# v1_0.net
KiCad netlist of a schematic drawn in EAGLE
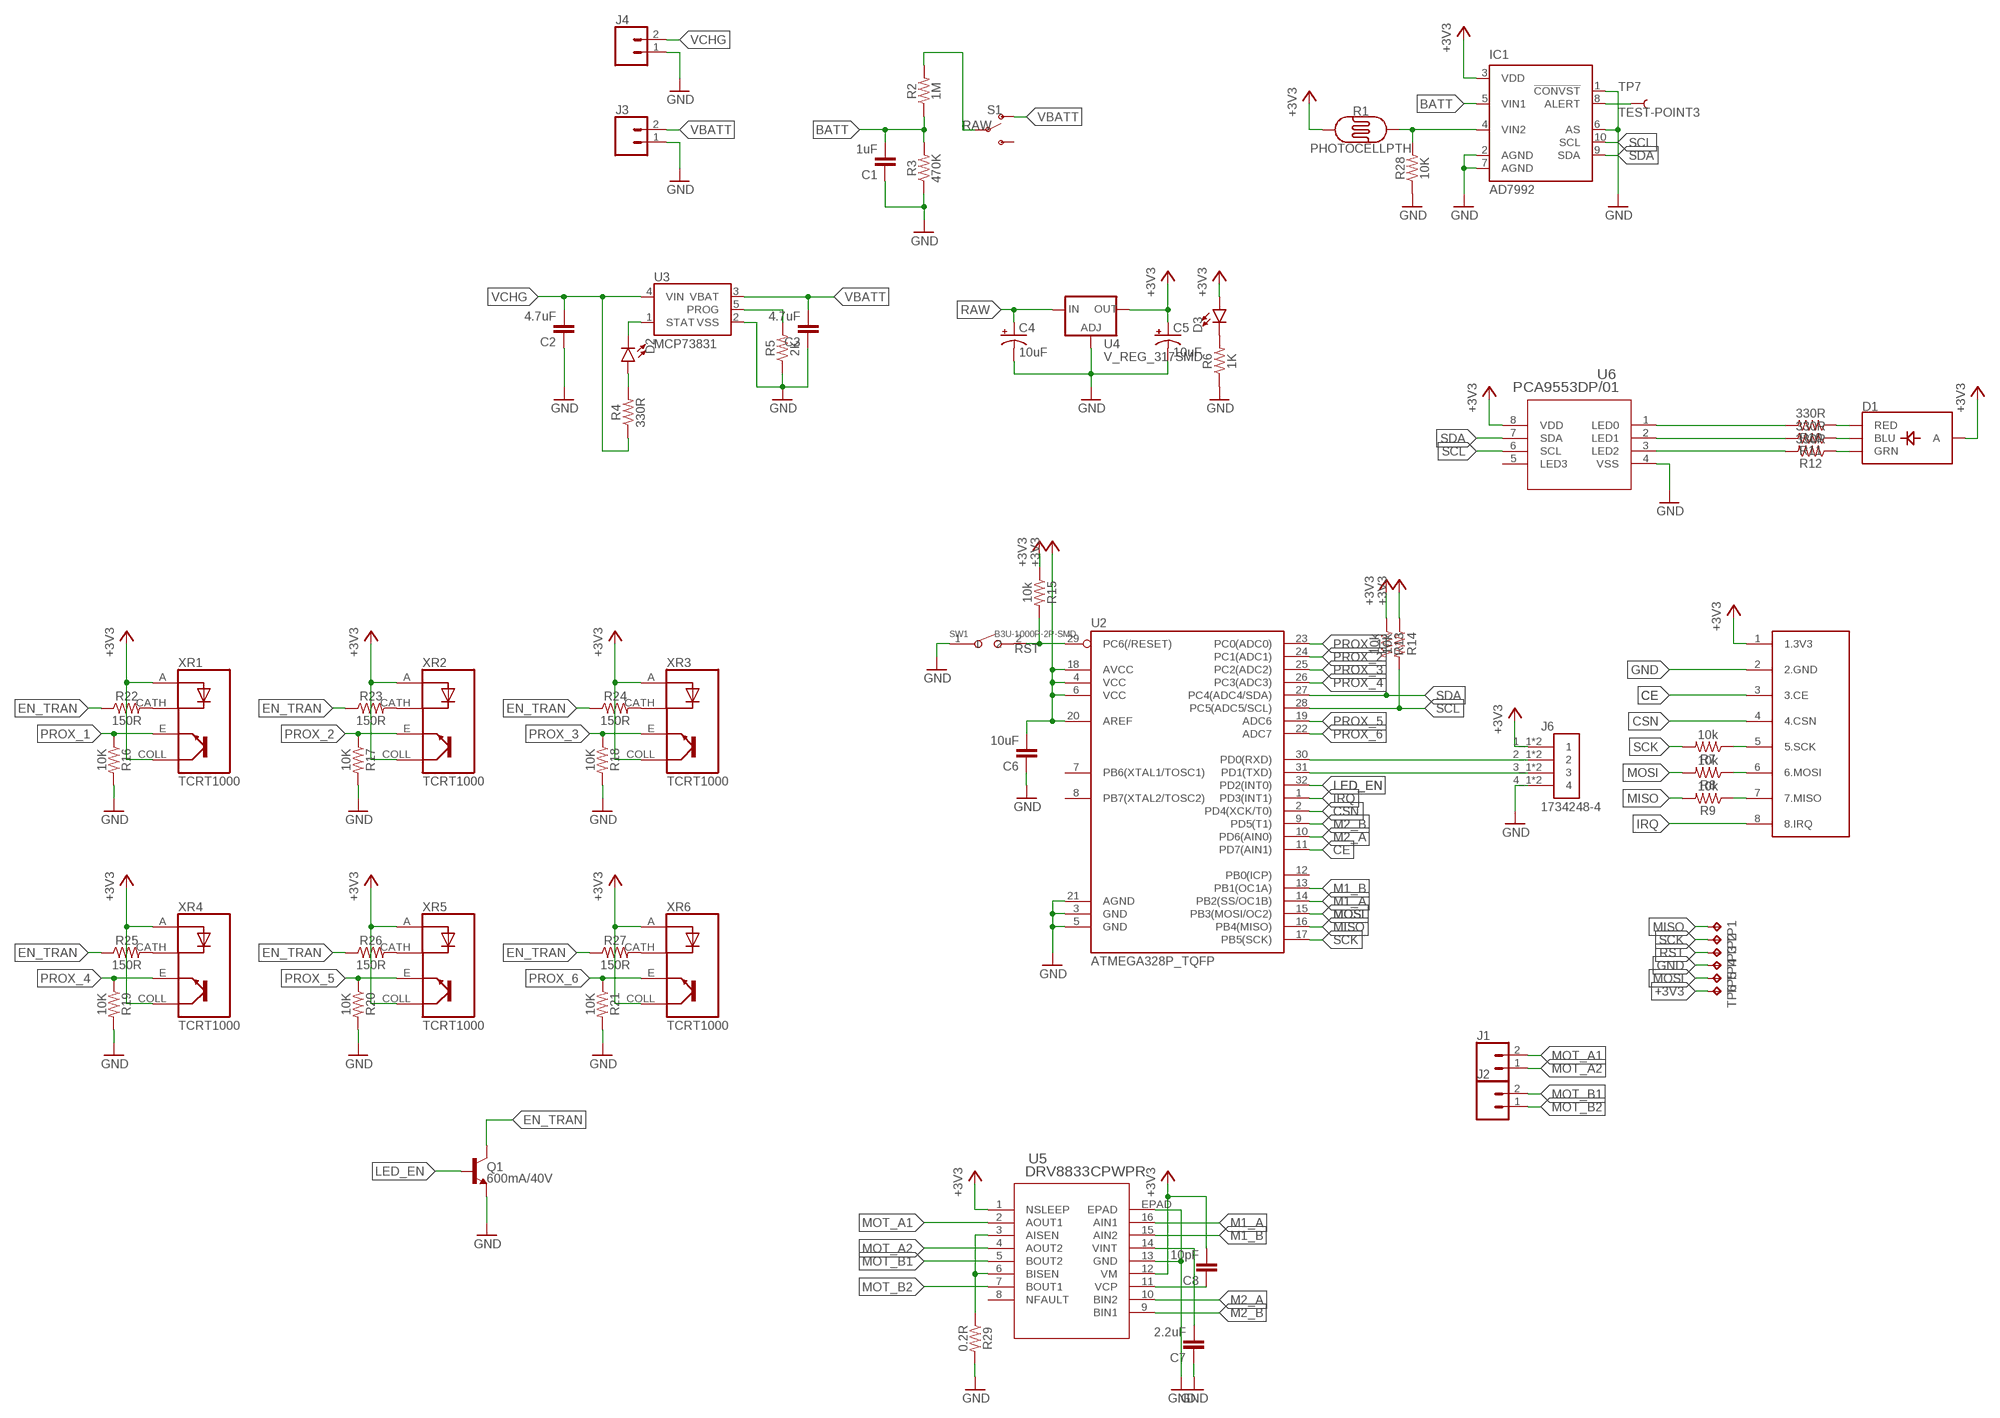
[diagram p0: schematic, sheet 1]

(export (version "E")
  (design (tool "Eeschema 10.0.6"))
  (components
    (comp (ref "C1")
      (value "1uF")
      (footprint "eagle-import:C0603")
      (libsource (lib "eagle-import") (part "C-EUC0603"))
    )
    (comp (ref "C2")
      (value "4.7uF")
      (footprint "eagle-import:C0603")
      (libsource (lib "eagle-import") (part "C-EUC0603"))
    )
    (comp (ref "C3")
      (value "4.7uF")
      (footprint "eagle-import:C0603")
      (libsource (lib "eagle-import") (part "C-EUC0603"))
    )
    (comp (ref "C4")
      (value "10uF")
      (footprint "eagle-import:EIA3216")
      (libsource (lib "eagle-import") (part "10UF-POLAR-EIA3216-16V-10%(TANT)"))
    )
    (comp (ref "C5")
      (value "10uF")
      (footprint "eagle-import:EIA3216")
      (libsource (lib "eagle-import") (part "10UF-POLAR-EIA3216-16V-10%(TANT)"))
    )
    (comp (ref "C6")
      (value "10uF")
      (footprint "eagle-import:C0603")
      (libsource (lib "eagle-import") (part "C-EUC0603"))
    )
    (comp (ref "C7")
      (value "2.2uF")
      (footprint "eagle-import:C0603")
      (libsource (lib "eagle-import") (part "C-EUC0603"))
    )
    (comp (ref "C8")
      (value "10pF")
      (footprint "eagle-import:C0603")
      (libsource (lib "eagle-import") (part "C-EUC0603"))
    )
    (comp (ref "D1")
      (value "LED-RGB-CASMD")
      (footprint "eagle-import:LED-TRICOLOR-SMD")
      (libsource (lib "eagle-import") (part "LED-RGB-CASMD"))
    )
    (comp (ref "D2")
      (value "LED0603")
      (footprint "eagle-import:LED-0603")
      (libsource (lib "eagle-import") (part "LED0603"))
    )
    (comp (ref "D3")
      (value "LED0603")
      (footprint "eagle-import:LED-0603")
      (libsource (lib "eagle-import") (part "LED0603"))
    )
    (comp (ref "IC1")
      (value "AD7992")
      (footprint "eagle-import:MSOP10")
      (fields (field (name "MPN") "AD7992BRMZ-0"))
      (libsource (lib "eagle-import") (part "AD7992"))
    )
    (comp (ref "J1")
      (value "CONN_02")
      (footprint "eagle-import:1X02")
      (libsource (lib "eagle-import") (part "CONN_02"))
    )
    (comp (ref "J2")
      (value "CONN_02")
      (footprint "eagle-import:1X02")
      (libsource (lib "eagle-import") (part "CONN_02"))
    )
    (comp (ref "J3")
      (value "CONN_02")
      (footprint "eagle-import:1X02")
      (libsource (lib "eagle-import") (part "CONN_02"))
    )
    (comp (ref "J4")
      (value "CONN_02")
      (footprint "eagle-import:1X02")
      (libsource (lib "eagle-import") (part "CONN_02"))
    )
    (comp (ref "J6")
      (value "1734248-4")
      (footprint "eagle-import:TE_1734248-4")
      (fields (field (name "DIGI-KEY_PART_NUMBER") "A101414CT-ND") (field (name "MF") "TE Connectivity"))
      (libsource (lib "eagle-import") (part "1734248-4"))
    )
    (comp (ref "Q1")
      (value "600mA/40V")
      (footprint "eagle-import:SOT23-3")
      (libsource (lib "eagle-import") (part "TRANS_NPN-MMBT2222AL"))
    )
    (comp (ref "R1")
      (value "PHOTOCELLPTH")
      (footprint "eagle-import:PHOTOCELL")
      (libsource (lib "eagle-import") (part "PHOTOCELLPTH"))
    )
    (comp (ref "R2")
      (value "1M")
      (footprint "eagle-import:0402")
      (libsource (lib "eagle-import") (part "RESISTOR0402"))
    )
    (comp (ref "R3")
      (value "470K")
      (footprint "eagle-import:0402")
      (libsource (lib "eagle-import") (part "RESISTOR0402"))
    )
    (comp (ref "R4")
      (value "330R")
      (footprint "eagle-import:0402")
      (libsource (lib "eagle-import") (part "RESISTOR0402"))
    )
    (comp (ref "R5")
      (value "2K")
      (footprint "eagle-import:0402")
      (libsource (lib "eagle-import") (part "RESISTOR0402"))
    )
    (comp (ref "R6")
      (value "1K")
      (footprint "eagle-import:0402")
      (libsource (lib "eagle-import") (part "RESISTOR0402"))
    )
    (comp (ref "R7")
      (value "10k")
      (footprint "eagle-import:0402")
      (libsource (lib "eagle-import") (part "RESISTOR0402"))
    )
    (comp (ref "R8")
      (value "10k")
      (footprint "eagle-import:0402")
      (libsource (lib "eagle-import") (part "RESISTOR0402"))
    )
    (comp (ref "R9")
      (value "10k")
      (footprint "eagle-import:0402")
      (libsource (lib "eagle-import") (part "RESISTOR0402"))
    )
    (comp (ref "R10")
      (value "330R")
      (footprint "eagle-import:0402")
      (libsource (lib "eagle-import") (part "RESISTOR0402"))
    )
    (comp (ref "R11")
      (value "330R")
      (footprint "eagle-import:0402")
      (libsource (lib "eagle-import") (part "RESISTOR0402"))
    )
    (comp (ref "R12")
      (value "330R")
      (footprint "eagle-import:0402")
      (libsource (lib "eagle-import") (part "RESISTOR0402"))
    )
    (comp (ref "R13")
      (value "10k")
      (footprint "eagle-import:0402")
      (libsource (lib "eagle-import") (part "RESISTOR0402"))
    )
    (comp (ref "R14")
      (value "10k")
      (footprint "eagle-import:0402")
      (libsource (lib "eagle-import") (part "RESISTOR0402"))
    )
    (comp (ref "R15")
      (value "10k")
      (footprint "eagle-import:0402")
      (libsource (lib "eagle-import") (part "RESISTOR0402"))
    )
    (comp (ref "R16")
      (value "10K")
      (footprint "eagle-import:0402")
      (libsource (lib "eagle-import") (part "RESISTOR0402"))
    )
    (comp (ref "R17")
      (value "10K")
      (footprint "eagle-import:0402")
      (libsource (lib "eagle-import") (part "RESISTOR0402"))
    )
    (comp (ref "R18")
      (value "10K")
      (footprint "eagle-import:0402")
      (libsource (lib "eagle-import") (part "RESISTOR0402"))
    )
    (comp (ref "R19")
      (value "10K")
      (footprint "eagle-import:0402")
      (libsource (lib "eagle-import") (part "RESISTOR0402"))
    )
    (comp (ref "R20")
      (value "10K")
      (footprint "eagle-import:0402")
      (libsource (lib "eagle-import") (part "RESISTOR0402"))
    )
    (comp (ref "R21")
      (value "10K")
      (footprint "eagle-import:0402")
      (libsource (lib "eagle-import") (part "RESISTOR0402"))
    )
    (comp (ref "R22")
      (value "150R")
      (footprint "eagle-import:0402")
      (libsource (lib "eagle-import") (part "RESISTOR0402"))
    )
    (comp (ref "R23")
      (value "150R")
      (footprint "eagle-import:0402")
      (libsource (lib "eagle-import") (part "RESISTOR0402"))
    )
    (comp (ref "R24")
      (value "150R")
      (footprint "eagle-import:0402")
      (libsource (lib "eagle-import") (part "RESISTOR0402"))
    )
    (comp (ref "R25")
      (value "150R")
      (footprint "eagle-import:0402")
      (libsource (lib "eagle-import") (part "RESISTOR0402"))
    )
    (comp (ref "R26")
      (value "150R")
      (footprint "eagle-import:0402")
      (libsource (lib "eagle-import") (part "RESISTOR0402"))
    )
    (comp (ref "R27")
      (value "150R")
      (footprint "eagle-import:0402")
      (libsource (lib "eagle-import") (part "RESISTOR0402"))
    )
    (comp (ref "R28")
      (value "10K")
      (footprint "eagle-import:0402")
      (libsource (lib "eagle-import") (part "RESISTOR0402"))
    )
    (comp (ref "R29")
      (value "0.2R")
      (footprint "eagle-import:0402")
      (libsource (lib "eagle-import") (part "RESISTOR0402"))
    )
    (comp (ref "S1")
      (value "SWITCH-SPDT-SMD-RIGHT-ANGLE")
      (footprint "eagle-import:SWITCH_SPST_SMD_A")
      (libsource (lib "eagle-import") (part "SWITCH-SPDT-SMD-RIGHT-ANGLE"))
    )
    (comp (ref "SW1")
      (value "B3U-1000P-2P-SMD")
      (footprint "eagle-import:SW2-2.6-3.0X2.5X1.2+0.4MM")
      (libsource (lib "eagle-import") (part "SMD-BUTTON(2P-3.0X2.5X1.2+0.4MM)-B3U-1000P-2P-SMD"))
    )
    (comp (ref "TP1")
      (value "TPB1,27")
      (footprint "eagle-import:B1,27")
      (libsource (lib "eagle-import") (part "TPB1,27"))
    )
    (comp (ref "TP2")
      (value "TPB1,27")
      (footprint "eagle-import:B1,27")
      (libsource (lib "eagle-import") (part "TPB1,27"))
    )
    (comp (ref "TP3")
      (value "TPB1,27")
      (footprint "eagle-import:B1,27")
      (libsource (lib "eagle-import") (part "TPB1,27"))
    )
    (comp (ref "TP4")
      (value "TPB1,27")
      (footprint "eagle-import:B1,27")
      (libsource (lib "eagle-import") (part "TPB1,27"))
    )
    (comp (ref "TP5")
      (value "TPB1,27")
      (footprint "eagle-import:B1,27")
      (libsource (lib "eagle-import") (part "TPB1,27"))
    )
    (comp (ref "TP6")
      (value "TPB1,27")
      (footprint "eagle-import:B1,27")
      (libsource (lib "eagle-import") (part "TPB1,27"))
    )
    (comp (ref "TP7")
      (value "TEST-POINT3")
      (footprint "eagle-import:PAD.03X.03")
      (libsource (lib "eagle-import") (part "TEST-POINT3"))
    )
    (comp (ref "U$1")
      (value "NRF24L01+")
      (footprint "eagle-import:NRF24L01+")
      (libsource (lib "eagle-import") (part "NRF24L01+"))
    )
    (comp (ref "U2")
      (value "ATMEGA328P_TQFP")
      (footprint "eagle-import:TQFP32-08")
      (libsource (lib "eagle-import") (part "ATMEGA328P_TQFP"))
    )
    (comp (ref "U3")
      (value "MCP73831")
      (footprint "eagle-import:SOT23-5")
      (libsource (lib "eagle-import") (part "MCP73831"))
    )
    (comp (ref "U4")
      (value "V_REG_317SMD")
      (footprint "eagle-import:SOT223")
      (libsource (lib "eagle-import") (part "V_REG_317SMD"))
    )
    (comp (ref "U5")
      (value "DRV8833CPWPR")
      (footprint "eagle-import:PWP16_2P31X2P46")
      (libsource (lib "eagle-import") (part "DRV8833CPWPR"))
    )
    (comp (ref "U6")
      (value "PCA9553DP/01")
      (footprint "eagle-import:SOT505-1")
      (fields (field (name "MANUFACTURER_PART_NUMBER") "PCA9553DP01"))
      (libsource (lib "eagle-import") (part "PCA9553DP/01"))
    )
    (comp (ref "XR1")
      (value "TCRT1000")
      (footprint "eagle-import:XDCR_TCRT1000")
      (fields (field (name "MF") "Vishay"))
      (libsource (lib "eagle-import") (part "TCRT1000"))
    )
    (comp (ref "XR2")
      (value "TCRT1000")
      (footprint "eagle-import:XDCR_TCRT1000")
      (fields (field (name "MF") "Vishay"))
      (libsource (lib "eagle-import") (part "TCRT1000"))
    )
    (comp (ref "XR3")
      (value "TCRT1000")
      (footprint "eagle-import:XDCR_TCRT1000")
      (fields (field (name "MF") "Vishay"))
      (libsource (lib "eagle-import") (part "TCRT1000"))
    )
    (comp (ref "XR4")
      (value "TCRT1000")
      (footprint "eagle-import:XDCR_TCRT1000")
      (fields (field (name "MF") "Vishay"))
      (libsource (lib "eagle-import") (part "TCRT1000"))
    )
    (comp (ref "XR5")
      (value "TCRT1000")
      (footprint "eagle-import:XDCR_TCRT1000")
      (fields (field (name "MF") "Vishay"))
      (libsource (lib "eagle-import") (part "TCRT1000"))
    )
    (comp (ref "XR6")
      (value "TCRT1000")
      (footprint "eagle-import:XDCR_TCRT1000")
      (fields (field (name "MF") "Vishay"))
      (libsource (lib "eagle-import") (part "TCRT1000"))
    )
  )
  (nets
    (net (code "1") (name "+3V3") (class "Default")
      (node (ref "C5") (pin "+") (pinfunction "+_+") (pintype "passive"))
      (node (ref "C6") (pin "2") (pinfunction "2_2") (pintype "passive"))
      (node (ref "C8") (pin "2") (pinfunction "2_2") (pintype "passive"))
      (node (ref "D1") (pin "A") (pinfunction "A_A") (pintype "bidirectional"))
      (node (ref "D3") (pin "A") (pinfunction "A_A") (pintype "passive"))
      (node (ref "IC1") (pin "3") (pinfunction "VDD_3") (pintype "power_in"))
      (node (ref "J6") (pin "1_1") (pinfunction "1_1_1") (pintype "passive"))
      (node (ref "J6") (pin "1_2") (pinfunction "1_1_2") (pintype "passive"))
      (node (ref "R1") (pin "1") (pinfunction "P$1_1") (pintype "bidirectional"))
      (node (ref "R13") (pin "1") (pinfunction "1_1") (pintype "passive"))
      (node (ref "R14") (pin "1") (pinfunction "1_1") (pintype "passive"))
      (node (ref "R15") (pin "1") (pinfunction "1_1") (pintype "passive"))
      (node (ref "TP6") (pin "TP") (pinfunction "TP_TP") (pintype "input"))
      (node (ref "U$1") (pin "1") (pinfunction "1.3V3_1") (pintype "bidirectional"))
      (node (ref "U2") (pin "18") (pinfunction "AVCC_18") (pintype "bidirectional"))
      (node (ref "U2") (pin "20") (pinfunction "AREF_20") (pintype "bidirectional"))
      (node (ref "U2") (pin "4") (pinfunction "VCC_4") (pintype "bidirectional"))
      (node (ref "U2") (pin "6") (pinfunction "VCC_6") (pintype "bidirectional"))
      (node (ref "U4") (pin "2") (pinfunction "OUT_2") (pintype "output"))
      (node (ref "U5") (pin "1") (pinfunction "NSLEEP_1") (pintype "input"))
      (node (ref "U5") (pin "12") (pinfunction "VM_12") (pintype "power_in"))
      (node (ref "U6") (pin "8") (pinfunction "VDD_8") (pintype "passive"))
      (node (ref "XR1") (pin "A") (pinfunction "A_A") (pintype "passive"))
      (node (ref "XR1") (pin "COLL") (pinfunction "CO_COLL") (pintype "passive"))
      (node (ref "XR2") (pin "A") (pinfunction "A_A") (pintype "passive"))
      (node (ref "XR2") (pin "COLL") (pinfunction "CO_COLL") (pintype "passive"))
      (node (ref "XR3") (pin "A") (pinfunction "A_A") (pintype "passive"))
      (node (ref "XR3") (pin "COLL") (pinfunction "CO_COLL") (pintype "passive"))
      (node (ref "XR4") (pin "A") (pinfunction "A_A") (pintype "passive"))
      (node (ref "XR4") (pin "COLL") (pinfunction "CO_COLL") (pintype "passive"))
      (node (ref "XR5") (pin "A") (pinfunction "A_A") (pintype "passive"))
      (node (ref "XR5") (pin "COLL") (pinfunction "CO_COLL") (pintype "passive"))
      (node (ref "XR6") (pin "A") (pinfunction "A_A") (pintype "passive"))
      (node (ref "XR6") (pin "COLL") (pinfunction "CO_COLL") (pintype "passive"))
    )
    (net (code "2") (name "BATT") (class "Default")
      (node (ref "C1") (pin "2") (pinfunction "2_2") (pintype "passive"))
      (node (ref "IC1") (pin "5") (pinfunction "VIN1_5") (pintype "input"))
      (node (ref "R2") (pin "1") (pinfunction "1_1") (pintype "passive"))
      (node (ref "R3") (pin "2") (pinfunction "2_2") (pintype "passive"))
    )
    (net (code "3") (name "CE") (class "Default")
      (node (ref "U$1") (pin "3") (pinfunction "3.CE_3") (pintype "bidirectional"))
      (node (ref "U2") (pin "11") (pinfunction "PD7(AIN1)_11") (pintype "bidirectional"))
    )
    (net (code "4") (name "CSN") (class "Default")
      (node (ref "U$1") (pin "4") (pinfunction "4.CSN_4") (pintype "bidirectional"))
      (node (ref "U2") (pin "2") (pinfunction "PD4(XCK/T0)_2") (pintype "bidirectional"))
    )
    (net (code "5") (name "EN_TRAN") (class "Default")
      (node (ref "Q1") (pin "3") (pinfunction "C_3") (pintype "passive"))
      (node (ref "R22") (pin "1") (pinfunction "1_1") (pintype "passive"))
      (node (ref "R23") (pin "1") (pinfunction "1_1") (pintype "passive"))
      (node (ref "R24") (pin "1") (pinfunction "1_1") (pintype "passive"))
      (node (ref "R25") (pin "1") (pinfunction "1_1") (pintype "passive"))
      (node (ref "R26") (pin "1") (pinfunction "1_1") (pintype "passive"))
      (node (ref "R27") (pin "1") (pinfunction "1_1") (pintype "passive"))
    )
    (net (code "6") (name "GND") (class "Default")
      (node (ref "C1") (pin "1") (pinfunction "1_1") (pintype "passive"))
      (node (ref "C2") (pin "1") (pinfunction "1_1") (pintype "passive"))
      (node (ref "C3") (pin "1") (pinfunction "1_1") (pintype "passive"))
      (node (ref "C4") (pin "-") (pinfunction "-_-") (pintype "passive"))
      (node (ref "C5") (pin "-") (pinfunction "-_-") (pintype "passive"))
      (node (ref "C6") (pin "1") (pinfunction "1_1") (pintype "passive"))
      (node (ref "C7") (pin "1") (pinfunction "1_1") (pintype "passive"))
      (node (ref "IC1") (pin "1") (pinfunction "~{CONVST}_1") (pintype "input"))
      (node (ref "IC1") (pin "2") (pinfunction "AGND_2") (pintype "power_in"))
      (node (ref "IC1") (pin "6") (pinfunction "AS_6") (pintype "input"))
      (node (ref "IC1") (pin "7") (pinfunction "AGND_7") (pintype "power_in"))
      (node (ref "J3") (pin "1") (pinfunction "1_1") (pintype "passive"))
      (node (ref "J4") (pin "1") (pinfunction "1_1") (pintype "passive"))
      (node (ref "J6") (pin "4_1") (pinfunction "4_4_1") (pintype "passive"))
      (node (ref "J6") (pin "4_2") (pinfunction "4_4_2") (pintype "passive"))
      (node (ref "Q1") (pin "2") (pinfunction "E_2") (pintype "passive"))
      (node (ref "R16") (pin "2") (pinfunction "2_2") (pintype "passive"))
      (node (ref "R17") (pin "2") (pinfunction "2_2") (pintype "passive"))
      (node (ref "R18") (pin "2") (pinfunction "2_2") (pintype "passive"))
      (node (ref "R19") (pin "2") (pinfunction "2_2") (pintype "passive"))
      (node (ref "R20") (pin "2") (pinfunction "2_2") (pintype "passive"))
      (node (ref "R21") (pin "2") (pinfunction "2_2") (pintype "passive"))
      (node (ref "R28") (pin "1") (pinfunction "1_1") (pintype "passive"))
      (node (ref "R29") (pin "2") (pinfunction "2_2") (pintype "passive"))
      (node (ref "R3") (pin "1") (pinfunction "1_1") (pintype "passive"))
      (node (ref "R5") (pin "1") (pinfunction "1_1") (pintype "passive"))
      (node (ref "R6") (pin "1") (pinfunction "1_1") (pintype "passive"))
      (node (ref "SW1") (pin "1") (pinfunction "1_1") (pintype "bidirectional"))
      (node (ref "TP4") (pin "TP") (pinfunction "TP_TP") (pintype "input"))
      (node (ref "U$1") (pin "2") (pinfunction "2.GND_2") (pintype "bidirectional"))
      (node (ref "U2") (pin "21") (pinfunction "AGND_21") (pintype "bidirectional"))
      (node (ref "U2") (pin "3") (pinfunction "GND_3") (pintype "bidirectional"))
      (node (ref "U2") (pin "5") (pinfunction "GND_5") (pintype "bidirectional"))
      (node (ref "U3") (pin "2") (pinfunction "VSS_2") (pintype "power_in"))
      (node (ref "U4") (pin "1") (pinfunction "ADJ_1") (pintype "input"))
      (node (ref "U5") (pin "13") (pinfunction "GND_13") (pintype "power_in"))
      (node (ref "U5") (pin "EPAD") (pinfunction "EPAD_EPAD") (pintype "passive"))
      (node (ref "U6") (pin "4") (pinfunction "VSS_4") (pintype "passive"))
    )
    (net (code "7") (name "IRQ") (class "Default")
      (node (ref "U$1") (pin "8") (pinfunction "8.IRQ_8") (pintype "bidirectional"))
      (node (ref "U2") (pin "1") (pinfunction "PD3(INT1)_1") (pintype "bidirectional"))
    )
    (net (code "8") (name "LED_EN") (class "Default")
      (node (ref "Q1") (pin "1") (pinfunction "B_1") (pintype "passive"))
      (node (ref "U2") (pin "32") (pinfunction "PD2(INT0)_32") (pintype "bidirectional"))
    )
    (net (code "9") (name "M1_A") (class "Default")
      (node (ref "U2") (pin "14") (pinfunction "PB2(SS/OC1B)_14") (pintype "bidirectional"))
      (node (ref "U5") (pin "16") (pinfunction "AIN1_16") (pintype "input"))
    )
    (net (code "10") (name "M1_B") (class "Default")
      (node (ref "U2") (pin "13") (pinfunction "PB1(OC1A)_13") (pintype "bidirectional"))
      (node (ref "U5") (pin "15") (pinfunction "AIN2_15") (pintype "input"))
    )
    (net (code "11") (name "M2_A") (class "Default")
      (node (ref "U2") (pin "10") (pinfunction "PD6(AIN0)_10") (pintype "bidirectional"))
      (node (ref "U5") (pin "10") (pinfunction "BIN2_10") (pintype "input"))
    )
    (net (code "12") (name "M2_B") (class "Default")
      (node (ref "U2") (pin "9") (pinfunction "PD5(T1)_9") (pintype "bidirectional"))
      (node (ref "U5") (pin "9") (pinfunction "BIN1_9") (pintype "input"))
    )
    (net (code "13") (name "MISO") (class "Default")
      (node (ref "R9") (pin "2") (pinfunction "2_2") (pintype "passive"))
      (node (ref "TP1") (pin "TP") (pinfunction "TP_TP") (pintype "input"))
      (node (ref "U2") (pin "16") (pinfunction "PB4(MISO)_16") (pintype "bidirectional"))
    )
    (net (code "14") (name "MOSI") (class "Default")
      (node (ref "R8") (pin "2") (pinfunction "2_2") (pintype "passive"))
      (node (ref "TP5") (pin "TP") (pinfunction "TP_TP") (pintype "input"))
      (node (ref "U2") (pin "15") (pinfunction "PB3(MOSI/OC2)_15") (pintype "bidirectional"))
    )
    (net (code "15") (name "MOT_A1") (class "Default")
      (node (ref "J1") (pin "2") (pinfunction "2_2") (pintype "passive"))
      (node (ref "U5") (pin "2") (pinfunction "AOUT1_2") (pintype "output"))
    )
    (net (code "16") (name "MOT_A2") (class "Default")
      (node (ref "J1") (pin "1") (pinfunction "1_1") (pintype "passive"))
      (node (ref "U5") (pin "4") (pinfunction "AOUT2_4") (pintype "output"))
    )
    (net (code "17") (name "MOT_B1") (class "Default")
      (node (ref "J2") (pin "2") (pinfunction "2_2") (pintype "passive"))
      (node (ref "U5") (pin "5") (pinfunction "BOUT2_5") (pintype "output"))
    )
    (net (code "18") (name "MOT_B2") (class "Default")
      (node (ref "J2") (pin "1") (pinfunction "1_1") (pintype "passive"))
      (node (ref "U5") (pin "7") (pinfunction "BOUT1_7") (pintype "output"))
    )
    (net (code "19") (name "Net-(D1-BLU)") (class "Default")
      (node (ref "D1") (pin "B") (pinfunction "BLU_B") (pintype "bidirectional"))
      (node (ref "R11") (pin "1") (pinfunction "1_1") (pintype "passive"))
    )
    (net (code "20") (name "Net-(D1-GRN)") (class "Default")
      (node (ref "D1") (pin "G") (pinfunction "GRN_G") (pintype "bidirectional"))
      (node (ref "R12") (pin "1") (pinfunction "1_1") (pintype "passive"))
    )
    (net (code "21") (name "Net-(D1-RED)") (class "Default")
      (node (ref "D1") (pin "R") (pinfunction "RED_R") (pintype "bidirectional"))
      (node (ref "R10") (pin "1") (pinfunction "1_1") (pintype "passive"))
    )
    (net (code "22") (name "Net-(D2-PadA)") (class "Default")
      (node (ref "D2") (pin "A") (pinfunction "A_A") (pintype "passive"))
      (node (ref "R4") (pin "2") (pinfunction "2_2") (pintype "passive"))
    )
    (net (code "23") (name "Net-(D3-PadC)") (class "Default")
      (node (ref "D3") (pin "C") (pinfunction "C_C") (pintype "passive"))
      (node (ref "R6") (pin "2") (pinfunction "2_2") (pintype "passive"))
    )
    (net (code "24") (name "Net-(IC1-ALERT)") (class "Default")
      (node (ref "IC1") (pin "8") (pinfunction "ALERT_8") (pintype "output"))
      (node (ref "TP7") (pin "P$1") (pinfunction "1_P$1") (pintype "bidirectional"))
    )
    (net (code "25") (name "Net-(IC1-VIN2)") (class "Default")
      (node (ref "IC1") (pin "4") (pinfunction "VIN2_4") (pintype "input"))
      (node (ref "R1") (pin "2") (pinfunction "P$2_2") (pintype "bidirectional"))
      (node (ref "R28") (pin "2") (pinfunction "2_2") (pintype "passive"))
    )
    (net (code "26") (name "Net-(U$1-5.SCK)") (class "Default")
      (node (ref "R7") (pin "1") (pinfunction "1_1") (pintype "passive"))
      (node (ref "U$1") (pin "5") (pinfunction "5.SCK_5") (pintype "bidirectional"))
    )
    (net (code "27") (name "Net-(U$1-6.MOSI)") (class "Default")
      (node (ref "R8") (pin "1") (pinfunction "1_1") (pintype "passive"))
      (node (ref "U$1") (pin "6") (pinfunction "6.MOSI_6") (pintype "bidirectional"))
    )
    (net (code "28") (name "Net-(U$1-7.MISO)") (class "Default")
      (node (ref "R9") (pin "1") (pinfunction "1_1") (pintype "passive"))
      (node (ref "U$1") (pin "7") (pinfunction "7.MISO_7") (pintype "bidirectional"))
    )
    (net (code "29") (name "Net-(U2-PD0(RXD))") (class "Default")
      (node (ref "J6") (pin "2_1") (pinfunction "2_2_1") (pintype "passive"))
      (node (ref "J6") (pin "2_2") (pinfunction "2_2_2") (pintype "passive"))
      (node (ref "U2") (pin "30") (pinfunction "PD0(RXD)_30") (pintype "bidirectional"))
    )
    (net (code "30") (name "Net-(U2-PD1(TXD))") (class "Default")
      (node (ref "J6") (pin "3_1") (pinfunction "3_3_1") (pintype "passive"))
      (node (ref "J6") (pin "3_2") (pinfunction "3_3_2") (pintype "passive"))
      (node (ref "U2") (pin "31") (pinfunction "PD1(TXD)_31") (pintype "bidirectional"))
    )
    (net (code "31") (name "Net-(U3-PROG)") (class "Default")
      (node (ref "R5") (pin "2") (pinfunction "2_2") (pintype "passive"))
      (node (ref "U3") (pin "5") (pinfunction "PROG_5") (pintype "input"))
    )
    (net (code "32") (name "Net-(U3-STAT)") (class "Default")
      (node (ref "D2") (pin "C") (pinfunction "C_C") (pintype "passive"))
      (node (ref "U3") (pin "1") (pinfunction "STAT_1") (pintype "output"))
    )
    (net (code "33") (name "Net-(U5-AISEN)") (class "Default")
      (node (ref "R29") (pin "1") (pinfunction "1_1") (pintype "passive"))
      (node (ref "U5") (pin "3") (pinfunction "AISEN_3") (pintype "bidirectional"))
      (node (ref "U5") (pin "6") (pinfunction "BISEN_6") (pintype "bidirectional"))
    )
    (net (code "34") (name "Net-(U5-VCP)") (class "Default")
      (node (ref "C8") (pin "1") (pinfunction "1_1") (pintype "passive"))
      (node (ref "U5") (pin "11") (pinfunction "VCP_11") (pintype "bidirectional"))
    )
    (net (code "35") (name "Net-(U5-VINT)") (class "Default")
      (node (ref "C7") (pin "2") (pinfunction "2_2") (pintype "passive"))
      (node (ref "U5") (pin "14") (pinfunction "VINT_14") (pintype "power_in"))
    )
    (net (code "36") (name "Net-(U6-LED0)") (class "Default")
      (node (ref "R10") (pin "2") (pinfunction "2_2") (pintype "passive"))
      (node (ref "U6") (pin "1") (pinfunction "LED0_1") (pintype "passive"))
    )
    (net (code "37") (name "Net-(U6-LED1)") (class "Default")
      (node (ref "R11") (pin "2") (pinfunction "2_2") (pintype "passive"))
      (node (ref "U6") (pin "2") (pinfunction "LED1_2") (pintype "passive"))
    )
    (net (code "38") (name "Net-(U6-LED2)") (class "Default")
      (node (ref "R12") (pin "2") (pinfunction "2_2") (pintype "passive"))
      (node (ref "U6") (pin "3") (pinfunction "LED2_3") (pintype "passive"))
    )
    (net (code "39") (name "Net-(XR1-C)") (class "Default")
      (node (ref "R22") (pin "2") (pinfunction "2_2") (pintype "passive"))
      (node (ref "XR1") (pin "CATH") (pinfunction "C_CATH") (pintype "passive"))
    )
    (net (code "40") (name "Net-(XR2-C)") (class "Default")
      (node (ref "R23") (pin "2") (pinfunction "2_2") (pintype "passive"))
      (node (ref "XR2") (pin "CATH") (pinfunction "C_CATH") (pintype "passive"))
    )
    (net (code "41") (name "Net-(XR3-C)") (class "Default")
      (node (ref "R24") (pin "2") (pinfunction "2_2") (pintype "passive"))
      (node (ref "XR3") (pin "CATH") (pinfunction "C_CATH") (pintype "passive"))
    )
    (net (code "42") (name "Net-(XR4-C)") (class "Default")
      (node (ref "R25") (pin "2") (pinfunction "2_2") (pintype "passive"))
      (node (ref "XR4") (pin "CATH") (pinfunction "C_CATH") (pintype "passive"))
    )
    (net (code "43") (name "Net-(XR5-C)") (class "Default")
      (node (ref "R26") (pin "2") (pinfunction "2_2") (pintype "passive"))
      (node (ref "XR5") (pin "CATH") (pinfunction "C_CATH") (pintype "passive"))
    )
    (net (code "44") (name "Net-(XR6-C)") (class "Default")
      (node (ref "R27") (pin "2") (pinfunction "2_2") (pintype "passive"))
      (node (ref "XR6") (pin "CATH") (pinfunction "C_CATH") (pintype "passive"))
    )
    (net (code "45") (name "PROX_1") (class "Default")
      (node (ref "R16") (pin "1") (pinfunction "1_1") (pintype "passive"))
      (node (ref "U2") (pin "23") (pinfunction "PC0(ADC0)_23") (pintype "bidirectional"))
      (node (ref "XR1") (pin "E") (pinfunction "E_E") (pintype "passive"))
    )
    (net (code "46") (name "PROX_2") (class "Default")
      (node (ref "R17") (pin "1") (pinfunction "1_1") (pintype "passive"))
      (node (ref "U2") (pin "24") (pinfunction "PC1(ADC1)_24") (pintype "bidirectional"))
      (node (ref "XR2") (pin "E") (pinfunction "E_E") (pintype "passive"))
    )
    (net (code "47") (name "PROX_3") (class "Default")
      (node (ref "R18") (pin "1") (pinfunction "1_1") (pintype "passive"))
      (node (ref "U2") (pin "25") (pinfunction "PC2(ADC2)_25") (pintype "bidirectional"))
      (node (ref "XR3") (pin "E") (pinfunction "E_E") (pintype "passive"))
    )
    (net (code "48") (name "PROX_4") (class "Default")
      (node (ref "R19") (pin "1") (pinfunction "1_1") (pintype "passive"))
      (node (ref "U2") (pin "26") (pinfunction "PC3(ADC3)_26") (pintype "bidirectional"))
      (node (ref "XR4") (pin "E") (pinfunction "E_E") (pintype "passive"))
    )
    (net (code "49") (name "PROX_5") (class "Default")
      (node (ref "R20") (pin "1") (pinfunction "1_1") (pintype "passive"))
      (node (ref "U2") (pin "19") (pinfunction "ADC6_19") (pintype "bidirectional"))
      (node (ref "XR5") (pin "E") (pinfunction "E_E") (pintype "passive"))
    )
    (net (code "50") (name "PROX_6") (class "Default")
      (node (ref "R21") (pin "1") (pinfunction "1_1") (pintype "passive"))
      (node (ref "U2") (pin "22") (pinfunction "ADC7_22") (pintype "bidirectional"))
      (node (ref "XR6") (pin "E") (pinfunction "E_E") (pintype "passive"))
    )
    (net (code "51") (name "RAW") (class "Default")
      (node (ref "C4") (pin "+") (pinfunction "+_+") (pintype "passive"))
      (node (ref "R2") (pin "2") (pinfunction "2_2") (pintype "passive"))
      (node (ref "S1") (pin "2") (pinfunction "P_2") (pintype "passive"))
      (node (ref "U4") (pin "3") (pinfunction "IN_3") (pintype "input"))
    )
    (net (code "52") (name "RST") (class "Default")
      (node (ref "R15") (pin "2") (pinfunction "2_2") (pintype "passive"))
      (node (ref "SW1") (pin "2") (pinfunction "2_2") (pintype "bidirectional"))
      (node (ref "TP3") (pin "TP") (pinfunction "TP_TP") (pintype "input"))
      (node (ref "U2") (pin "29") (pinfunction "PC6(/RESET)_29") (pintype "bidirectional"))
    )
    (net (code "53") (name "SCK") (class "Default")
      (node (ref "R7") (pin "2") (pinfunction "2_2") (pintype "passive"))
      (node (ref "TP2") (pin "TP") (pinfunction "TP_TP") (pintype "input"))
      (node (ref "U2") (pin "17") (pinfunction "PB5(SCK)_17") (pintype "bidirectional"))
    )
    (net (code "54") (name "SCL") (class "Default")
      (node (ref "IC1") (pin "10") (pinfunction "SCL_10") (pintype "input"))
      (node (ref "R14") (pin "2") (pinfunction "2_2") (pintype "passive"))
      (node (ref "U2") (pin "28") (pinfunction "PC5(ADC5/SCL)_28") (pintype "bidirectional"))
      (node (ref "U6") (pin "6") (pinfunction "SCL_6") (pintype "passive"))
    )
    (net (code "55") (name "SDA") (class "Default")
      (node (ref "IC1") (pin "9") (pinfunction "SDA_9") (pintype "bidirectional"))
      (node (ref "R13") (pin "2") (pinfunction "2_2") (pintype "passive"))
      (node (ref "U2") (pin "27") (pinfunction "PC4(ADC4/SDA)_27") (pintype "bidirectional"))
      (node (ref "U6") (pin "7") (pinfunction "SDA_7") (pintype "passive"))
    )
    (net (code "56") (name "VBATT") (class "Default")
      (node (ref "C3") (pin "2") (pinfunction "2_2") (pintype "passive"))
      (node (ref "J3") (pin "2") (pinfunction "2_2") (pintype "passive"))
      (node (ref "S1") (pin "1") (pinfunction "O_1") (pintype "passive"))
      (node (ref "U3") (pin "3") (pinfunction "VBAT_3") (pintype "power_in"))
    )
    (net (code "57") (name "VCHG") (class "Default")
      (node (ref "C2") (pin "2") (pinfunction "2_2") (pintype "passive"))
      (node (ref "J4") (pin "2") (pinfunction "2_2") (pintype "passive"))
      (node (ref "R4") (pin "1") (pinfunction "1_1") (pintype "passive"))
      (node (ref "U3") (pin "4") (pinfunction "VIN_4") (pintype "power_in"))
    )
    (net (code "58") (name "unconnected-(S1-S-Pad3)") (class "Default")
      (node (ref "S1") (pin "3") (pinfunction "S_3") (pintype "passive"))
    )
    (net (code "59") (name "unconnected-(U2-PB0(ICP)-Pad12)") (class "Default")
      (node (ref "U2") (pin "12") (pinfunction "PB0(ICP)_12") (pintype "bidirectional"))
    )
    (net (code "60") (name "unconnected-(U2-PB6(XTAL1{slash}TOSC1)-Pad7)") (class "Default")
      (node (ref "U2") (pin "7") (pinfunction "PB6(XTAL1/TOSC1)_7") (pintype "bidirectional"))
    )
    (net (code "61") (name "unconnected-(U2-PB7(XTAL2{slash}TOSC2)-Pad8)") (class "Default")
      (node (ref "U2") (pin "8") (pinfunction "PB7(XTAL2/TOSC2)_8") (pintype "bidirectional"))
    )
    (net (code "62") (name "unconnected-(U5-NFAULT-Pad8)") (class "Default")
      (node (ref "U5") (pin "8") (pinfunction "NFAULT_8") (pintype "output"))
    )
    (net (code "63") (name "unconnected-(U6-LED3-Pad5)") (class "Default")
      (node (ref "U6") (pin "5") (pinfunction "LED3_5") (pintype "passive"))
    )
  )
)
